# 1_Power.net
KiCad netlist of a schematic drawn in Altium Designer
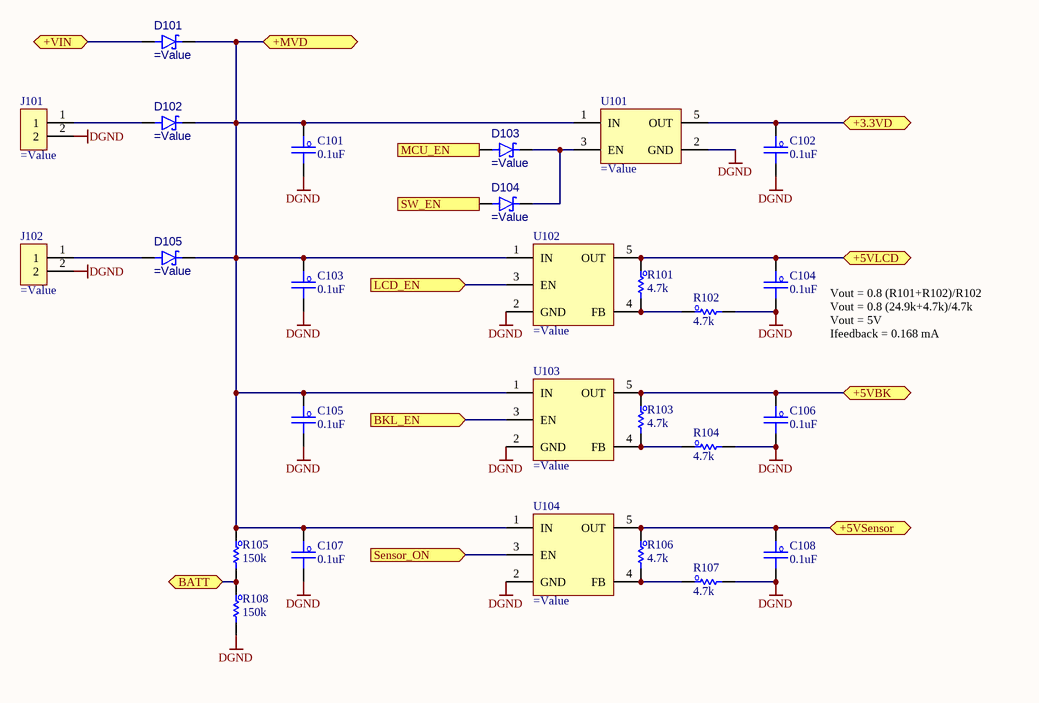
[diagram p0: 1_Power.SchDoc]

(export (version "E")
  (design (tool "Eeschema 10.0.6"))
  (components
    (comp (ref "C101")
      (value "0.1uF")
      (footprint "C_0603")
      (description "CAP CER 0.1UF 50V X7R 0603")
      (fields (field (name "MANUFACTURER") "KEMET") (field (name "PARTNUMBER") "C0603C104K5RACTU"))
      (libsource (lib "UUSymbol") (part "C_Capacitor"))
    )
    (comp (ref "C102")
      (value "0.1uF")
      (footprint "C_0603")
      (description "CAP CER 0.1UF 50V X7R 0603")
      (fields (field (name "MANUFACTURER") "KEMET") (field (name "PARTNUMBER") "C0603C104K5RACTU"))
      (libsource (lib "UUSymbol") (part "C_Capacitor"))
    )
    (comp (ref "C103")
      (value "0.1uF")
      (footprint "C_0603")
      (description "CAP CER 0.1UF 50V X7R 0603")
      (fields (field (name "MANUFACTURER") "KEMET") (field (name "PARTNUMBER") "C0603C104K5RACTU"))
      (libsource (lib "UUSymbol") (part "C_Capacitor"))
    )
    (comp (ref "C104")
      (value "0.1uF")
      (footprint "C_0603")
      (description "CAP CER 0.1UF 50V X7R 0603")
      (fields (field (name "MANUFACTURER") "KEMET") (field (name "PARTNUMBER") "C0603C104K5RACTU"))
      (libsource (lib "UUSymbol") (part "C_Capacitor"))
    )
    (comp (ref "C105")
      (value "0.1uF")
      (footprint "C_0603")
      (description "CAP CER 0.1UF 50V X7R 0603")
      (fields (field (name "MANUFACTURER") "KEMET") (field (name "PARTNUMBER") "C0603C104K5RACTU"))
      (libsource (lib "UUSymbol") (part "C_Capacitor"))
    )
    (comp (ref "C106")
      (value "0.1uF")
      (footprint "C_0603")
      (description "CAP CER 0.1UF 50V X7R 0603")
      (fields (field (name "MANUFACTURER") "KEMET") (field (name "PARTNUMBER") "C0603C104K5RACTU"))
      (libsource (lib "UUSymbol") (part "C_Capacitor"))
    )
    (comp (ref "C107")
      (value "0.1uF")
      (footprint "C_0603")
      (description "CAP CER 0.1UF 50V X7R 0603")
      (fields (field (name "MANUFACTURER") "KEMET") (field (name "PARTNUMBER") "C0603C104K5RACTU"))
      (libsource (lib "UUSymbol") (part "C_Capacitor"))
    )
    (comp (ref "C108")
      (value "0.1uF")
      (footprint "C_0603")
      (description "CAP CER 0.1UF 50V X7R 0603")
      (fields (field (name "MANUFACTURER") "KEMET") (field (name "PARTNUMBER") "C0603C104K5RACTU"))
      (libsource (lib "UUSymbol") (part "C_Capacitor"))
    )
    (comp (ref "D101")
      (value "~")
      (footprint "DIOM4325X250N")
      (description "DIODE SCHOTTKY 100V 3A DO214AC")
      (fields
        (field (name "MANUFACTURER") "Taiwan Semiconductor Corporation")
        (field (name "PARTNUMBER") "SK310A R2")
      )
      (libsource (lib "UUSymbol") (part "D_PW_SK310A"))
    )
    (comp (ref "D102")
      (value "~")
      (footprint "DIOM4325X250N")
      (description "DIODE SCHOTTKY 100V 3A DO214AC")
      (fields
        (field (name "MANUFACTURER") "Taiwan Semiconductor Corporation")
        (field (name "PARTNUMBER") "SK310A R2")
      )
      (libsource (lib "UUSymbol") (part "D_PW_SK310A"))
    )
    (comp (ref "D103")
      (value "~")
      (footprint "DIOM4325X250N")
      (description "DIODE SCHOTTKY 100V 3A DO214AC")
      (fields
        (field (name "MANUFACTURER") "Taiwan Semiconductor Corporation")
        (field (name "PARTNUMBER") "SK310A R2")
      )
      (libsource (lib "UUSymbol") (part "D_PW_SK310A"))
    )
    (comp (ref "D104")
      (value "~")
      (footprint "DIOM4325X250N")
      (description "DIODE SCHOTTKY 100V 3A DO214AC")
      (fields
        (field (name "MANUFACTURER") "Taiwan Semiconductor Corporation")
        (field (name "PARTNUMBER") "SK310A R2")
      )
      (libsource (lib "UUSymbol") (part "D_PW_SK310A"))
    )
    (comp (ref "D105")
      (value "~")
      (footprint "DIOM4325X250N")
      (description "DIODE SCHOTTKY 100V 3A DO214AC")
      (fields
        (field (name "MANUFACTURER") "Taiwan Semiconductor Corporation")
        (field (name "PARTNUMBER") "SK310A R2")
      )
      (libsource (lib "UUSymbol") (part "D_PW_SK310A"))
    )
    (comp (ref "J101")
      (value "~")
      (footprint "CON_2P_Header")
      (description "Connector 2 position")
      (fields
        (field (name "PARTNUMBER") "796866-2")
        (field (name "MANUFACTURER") "TE Connectivity AMP Connectors")
      )
      (libsource (lib "UUSymbol") (part "CON_2P_Heder"))
    )
    (comp (ref "J102")
      (value "~")
      (footprint "CON_2P_Header")
      (description "Connector 2 position")
      (fields
        (field (name "PARTNUMBER") "796866-2")
        (field (name "MANUFACTURER") "TE Connectivity AMP Connectors")
      )
      (libsource (lib "UUSymbol") (part "CON_2P_Heder"))
    )
    (comp (ref "R101")
      (value "4.7k")
      (footprint "R_0603")
      (description "RES 4.7K OHM 5% 1/10W 0603")
      (fields (field (name "MANUFACTURER") "Vishay Dale") (field (name "PARTNUMBER") "CRCW06034K70JNEBC"))
      (libsource (lib "UUSymbol") (part "R_Resister"))
    )
    (comp (ref "R102")
      (value "4.7k")
      (footprint "R_0603")
      (description "RES 4.7K OHM 5% 1/10W 0603")
      (fields (field (name "MANUFACTURER") "Vishay Dale") (field (name "PARTNUMBER") "CRCW06034K70JNEBC"))
      (libsource (lib "UUSymbol") (part "R_Resister"))
    )
    (comp (ref "R103")
      (value "4.7k")
      (footprint "R_0603")
      (description "RES 4.7K OHM 5% 1/10W 0603")
      (fields (field (name "MANUFACTURER") "Vishay Dale") (field (name "PARTNUMBER") "CRCW06034K70JNEBC"))
      (libsource (lib "UUSymbol") (part "R_Resister"))
    )
    (comp (ref "R104")
      (value "4.7k")
      (footprint "R_0603")
      (description "RES 4.7K OHM 5% 1/10W 0603")
      (fields (field (name "MANUFACTURER") "Vishay Dale") (field (name "PARTNUMBER") "CRCW06034K70JNEBC"))
      (libsource (lib "UUSymbol") (part "R_Resister"))
    )
    (comp (ref "R105")
      (value "150k")
      (footprint "R_0603")
      (description "RES SMD 150K OHM 1% 1/10W 0603")
      (fields (field (name "MANUFACTURER") "Vishay Dale") (field (name "PARTNUMBER") "CRCW0603150KFKEAC"))
      (libsource (lib "UUSymbol") (part "R_Resister"))
    )
    (comp (ref "R106")
      (value "4.7k")
      (footprint "R_0603")
      (description "RES 4.7K OHM 5% 1/10W 0603")
      (fields (field (name "MANUFACTURER") "Vishay Dale") (field (name "PARTNUMBER") "CRCW06034K70JNEBC"))
      (libsource (lib "UUSymbol") (part "R_Resister"))
    )
    (comp (ref "R107")
      (value "4.7k")
      (footprint "R_0603")
      (description "RES 4.7K OHM 5% 1/10W 0603")
      (fields (field (name "MANUFACTURER") "Vishay Dale") (field (name "PARTNUMBER") "CRCW06034K70JNEBC"))
      (libsource (lib "UUSymbol") (part "R_Resister"))
    )
    (comp (ref "R108")
      (value "150k")
      (footprint "R_0603")
      (description "RES SMD 150K OHM 1% 1/10W 0603")
      (fields (field (name "MANUFACTURER") "Vishay Dale") (field (name "PARTNUMBER") "CRCW0603150KFKEAC"))
      (libsource (lib "UUSymbol") (part "R_Resister"))
    )
    (comp (ref "U101")
      (value "~")
      (footprint "SOT95P280X125-5N")
      (description "IC REG LINEAR 3.3V 500MA 5SSOP")
      (fields (field (name "PARTNUMBER") "BU33SD5WG-TR") (field (name "MANUFACTURER") "Rohm Semiconductor"))
      (libsource (lib "UUSymbol") (part "IC_LDO_BU33SD5WG-TR"))
    )
    (comp (ref "U102")
      (value "~")
      (footprint "SOT95P280X145-5N")
      (fields (field (name "PARTNUMBER") "ZTP7001-00") (field (name "MANUFACTURER") "ZILLTEK"))
      (libsource (lib "UUSymbol") (part "IC_LDO_ZTP7001"))
    )
    (comp (ref "U103")
      (value "~")
      (footprint "SOT95P280X145-5N")
      (fields (field (name "PARTNUMBER") "ZTP7001-00") (field (name "MANUFACTURER") "ZILLTEK"))
      (libsource (lib "UUSymbol") (part "IC_LDO_ZTP7001"))
    )
    (comp (ref "U104")
      (value "~")
      (footprint "SOT95P280X145-5N")
      (fields (field (name "PARTNUMBER") "ZTP7001-00") (field (name "MANUFACTURER") "ZILLTEK"))
      (libsource (lib "UUSymbol") (part "IC_LDO_ZTP7001"))
    )
  )
  (nets
    (net (code "1") (name "/+3.3VD") (class "Default")
      (node (ref "C102") (pin "1") (pinfunction "1_1") (pintype "passive"))
      (node (ref "U101") (pin "5") (pinfunction "OUT_5") (pintype "passive"))
    )
    (net (code "2") (name "/+5VBK") (class "Default")
      (node (ref "C106") (pin "1") (pinfunction "1_1") (pintype "passive"))
      (node (ref "R103") (pin "1") (pinfunction "1_1") (pintype "passive"))
      (node (ref "U103") (pin "5") (pinfunction "OUT_5") (pintype "passive"))
    )
    (net (code "3") (name "/+5VLCD") (class "Default")
      (node (ref "C104") (pin "1") (pinfunction "1_1") (pintype "passive"))
      (node (ref "R101") (pin "1") (pinfunction "1_1") (pintype "passive"))
      (node (ref "U102") (pin "5") (pinfunction "OUT_5") (pintype "passive"))
    )
    (net (code "4") (name "/+5VSensor") (class "Default")
      (node (ref "C108") (pin "1") (pinfunction "1_1") (pintype "passive"))
      (node (ref "R106") (pin "1") (pinfunction "1_1") (pintype "passive"))
      (node (ref "U104") (pin "5") (pinfunction "OUT_5") (pintype "passive"))
    )
    (net (code "5") (name "/+MVD") (class "Default")
      (node (ref "C101") (pin "1") (pinfunction "1_1") (pintype "passive"))
      (node (ref "C103") (pin "1") (pinfunction "1_1") (pintype "passive"))
      (node (ref "C105") (pin "1") (pinfunction "1_1") (pintype "passive"))
      (node (ref "C107") (pin "1") (pinfunction "1_1") (pintype "passive"))
      (node (ref "D101") (pin "1") (pinfunction "1_1") (pintype "passive"))
      (node (ref "D102") (pin "1") (pinfunction "1_1") (pintype "passive"))
      (node (ref "D105") (pin "1") (pinfunction "1_1") (pintype "passive"))
      (node (ref "R105") (pin "1") (pinfunction "1_1") (pintype "passive"))
      (node (ref "U101") (pin "1") (pinfunction "IN_1") (pintype "passive"))
      (node (ref "U102") (pin "1") (pinfunction "IN_1") (pintype "passive"))
      (node (ref "U103") (pin "1") (pinfunction "IN_1") (pintype "passive"))
      (node (ref "U104") (pin "1") (pinfunction "IN_1") (pintype "passive"))
    )
    (net (code "6") (name "/+VIN") (class "Default")
      (node (ref "D101") (pin "2") (pinfunction "2_2") (pintype "passive"))
    )
    (net (code "7") (name "/BATT") (class "Default")
      (node (ref "R105") (pin "2") (pinfunction "2_2") (pintype "passive"))
      (node (ref "R108") (pin "1") (pinfunction "1_1") (pintype "passive"))
    )
    (net (code "8") (name "/BKL_EN") (class "Default")
      (node (ref "U103") (pin "3") (pinfunction "EN_3") (pintype "passive"))
    )
    (net (code "9") (name "/LCD_EN") (class "Default")
      (node (ref "U102") (pin "3") (pinfunction "EN_3") (pintype "passive"))
    )
    (net (code "10") (name "/MCU_EN") (class "Default")
      (node (ref "D103") (pin "2") (pinfunction "2_2") (pintype "passive"))
    )
    (net (code "11") (name "/SW_EN") (class "Default")
      (node (ref "D104") (pin "2") (pinfunction "2_2") (pintype "passive"))
    )
    (net (code "12") (name "/Sensor_ON") (class "Default")
      (node (ref "U104") (pin "3") (pinfunction "EN_3") (pintype "passive"))
    )
    (net (code "13") (name "DGND") (class "Default")
      (node (ref "C101") (pin "2") (pinfunction "2_2") (pintype "passive"))
      (node (ref "C102") (pin "2") (pinfunction "2_2") (pintype "passive"))
      (node (ref "C103") (pin "2") (pinfunction "2_2") (pintype "passive"))
      (node (ref "C104") (pin "2") (pinfunction "2_2") (pintype "passive"))
      (node (ref "C105") (pin "2") (pinfunction "2_2") (pintype "passive"))
      (node (ref "C106") (pin "2") (pinfunction "2_2") (pintype "passive"))
      (node (ref "C107") (pin "2") (pinfunction "2_2") (pintype "passive"))
      (node (ref "C108") (pin "2") (pinfunction "2_2") (pintype "passive"))
      (node (ref "J101") (pin "2") (pinfunction "2_2") (pintype "passive"))
      (node (ref "J102") (pin "2") (pinfunction "2_2") (pintype "passive"))
      (node (ref "R102") (pin "2") (pinfunction "2_2") (pintype "passive"))
      (node (ref "R104") (pin "2") (pinfunction "2_2") (pintype "passive"))
      (node (ref "R107") (pin "2") (pinfunction "2_2") (pintype "passive"))
      (node (ref "R108") (pin "2") (pinfunction "2_2") (pintype "passive"))
      (node (ref "U101") (pin "2") (pinfunction "GND_2") (pintype "passive"))
      (node (ref "U102") (pin "2") (pinfunction "GND_2") (pintype "passive"))
      (node (ref "U103") (pin "2") (pinfunction "GND_2") (pintype "passive"))
      (node (ref "U104") (pin "2") (pinfunction "GND_2") (pintype "passive"))
    )
    (net (code "14") (name "Net-(D102-Pad2)") (class "Default")
      (node (ref "D102") (pin "2") (pinfunction "2_2") (pintype "passive"))
      (node (ref "J101") (pin "1") (pinfunction "1_1") (pintype "passive"))
    )
    (net (code "15") (name "Net-(D105-Pad2)") (class "Default")
      (node (ref "D105") (pin "2") (pinfunction "2_2") (pintype "passive"))
      (node (ref "J102") (pin "1") (pinfunction "1_1") (pintype "passive"))
    )
    (net (code "16") (name "Net-(U101-EN)") (class "Default")
      (node (ref "D103") (pin "1") (pinfunction "1_1") (pintype "passive"))
      (node (ref "D104") (pin "1") (pinfunction "1_1") (pintype "passive"))
      (node (ref "U101") (pin "3") (pinfunction "EN_3") (pintype "passive"))
    )
    (net (code "17") (name "Net-(U102-FB)") (class "Default")
      (node (ref "R101") (pin "2") (pinfunction "2_2") (pintype "passive"))
      (node (ref "R102") (pin "1") (pinfunction "1_1") (pintype "passive"))
      (node (ref "U102") (pin "4") (pinfunction "FB_4") (pintype "passive"))
    )
    (net (code "18") (name "Net-(U103-FB)") (class "Default")
      (node (ref "R103") (pin "2") (pinfunction "2_2") (pintype "passive"))
      (node (ref "R104") (pin "1") (pinfunction "1_1") (pintype "passive"))
      (node (ref "U103") (pin "4") (pinfunction "FB_4") (pintype "passive"))
    )
    (net (code "19") (name "Net-(U104-FB)") (class "Default")
      (node (ref "R106") (pin "2") (pinfunction "2_2") (pintype "passive"))
      (node (ref "R107") (pin "1") (pinfunction "1_1") (pintype "passive"))
      (node (ref "U104") (pin "4") (pinfunction "FB_4") (pintype "passive"))
    )
  )
)
